# Battery_Shield.net
KiCad netlist of a schematic drawn in EAGLE
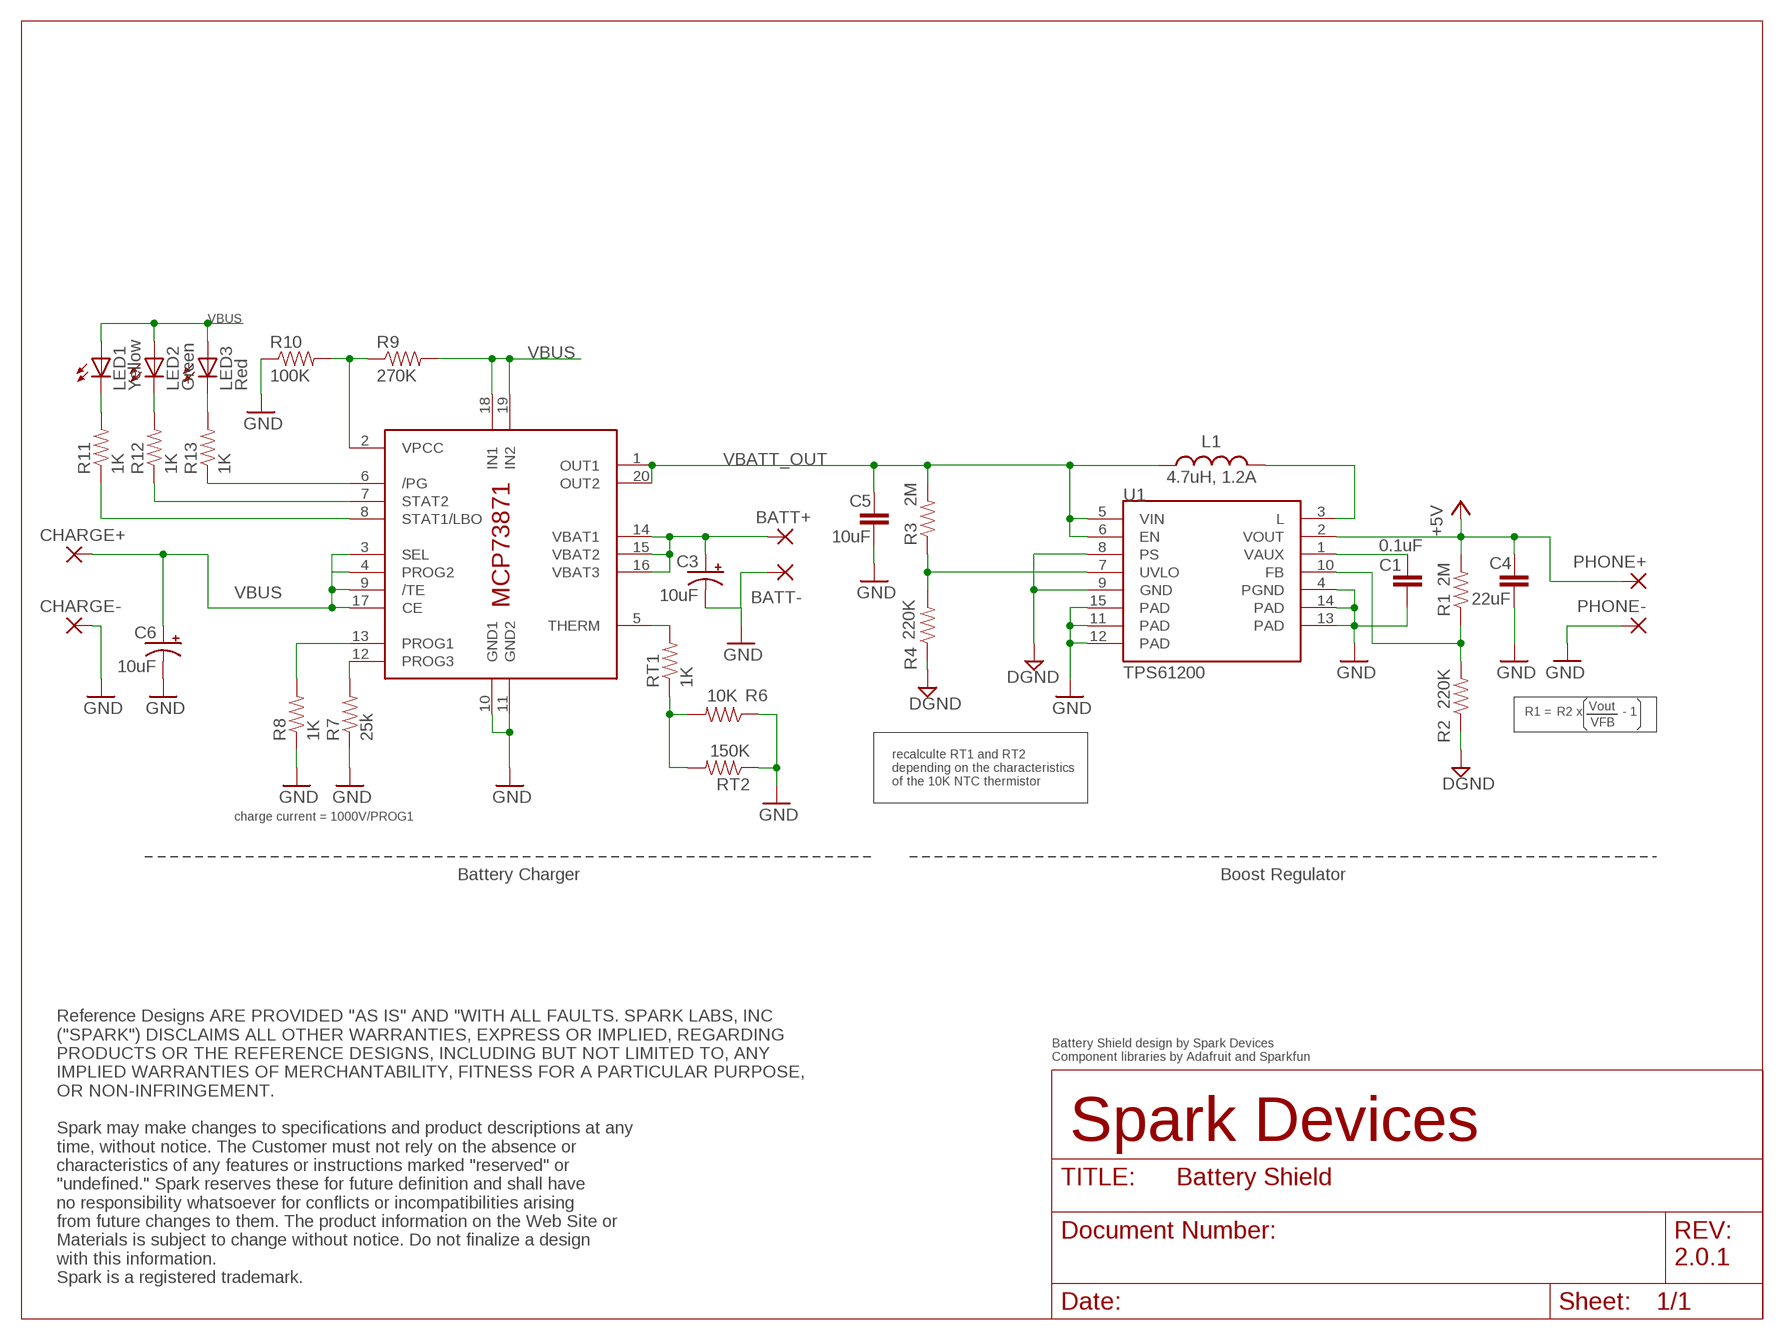
[diagram p0: schematic, sheet 1]

(export (version "E")
  (design (tool "Eeschema 10.0.6"))
  (components
    (comp (ref "BATT+")
      (value "WIREPAD2,15/1,0")
      (footprint "eagle-import:2,15_1,0")
      (libsource (lib "eagle-import") (part "WIREPAD2,15/1,0"))
    )
    (comp (ref "BATT-")
      (value "WIREPAD2,15/1,0")
      (footprint "eagle-import:2,15_1,0")
      (libsource (lib "eagle-import") (part "WIREPAD2,15/1,0"))
    )
    (comp (ref "C1")
      (value "0.1uF")
      (footprint "eagle-import:0402-CAP")
      (libsource (lib "eagle-import") (part "SparkFun-Passives_CAP0402-CAP"))
    )
    (comp (ref "C3")
      (value "10uF")
      (footprint "eagle-import:EIA3216")
      (libsource (lib "eagle-import") (part "10UF-16V-10%(TANT)"))
    )
    (comp (ref "C4")
      (value "22uF")
      (footprint "eagle-import:0805")
      (libsource (lib "eagle-import") (part "SparkFun-Passives_CAP0805"))
    )
    (comp (ref "C5")
      (value "10uF")
      (footprint "eagle-import:1206")
      (libsource (lib "eagle-import") (part "CAP1206"))
    )
    (comp (ref "C6")
      (value "10uF")
      (footprint "eagle-import:EIA3216")
      (fields (field (name "PROD_ID") "CAP-00811"))
      (libsource (lib "eagle-import") (part "10UF-16V-10%(TANT)"))
    )
    (comp (ref "CHARGE+")
      (value "WIREPAD2,15/1,0")
      (footprint "eagle-import:2,15_1,0")
      (libsource (lib "eagle-import") (part "WIREPAD2,15/1,0"))
    )
    (comp (ref "CHARGE-")
      (value "WIREPAD2,15/1,0")
      (footprint "eagle-import:2,15_1,0")
      (libsource (lib "eagle-import") (part "WIREPAD2,15/1,0"))
    )
    (comp (ref "IC1")
      (value "MCP73871")
      (footprint "eagle-import:QFN20")
      (libsource (lib "eagle-import") (part "MCP73871"))
    )
    (comp (ref "L1")
      (value "4.7uH, 1.2A")
      (footprint "eagle-import:CDRH2D09")
      (libsource (lib "eagle-import") (part "INDUCTOR."))
    )
    (comp (ref "LED1")
      (value "Yellow")
      (footprint "eagle-import:LED-0603")
      (libsource (lib "eagle-import") (part "LED0603"))
    )
    (comp (ref "LED2")
      (value "Green")
      (footprint "eagle-import:LED-0603")
      (libsource (lib "eagle-import") (part "LED0603"))
    )
    (comp (ref "LED3")
      (value "Red")
      (footprint "eagle-import:LED-0603")
      (libsource (lib "eagle-import") (part "LED0603"))
    )
    (comp (ref "PHONE+")
      (value "WIREPAD2,15/1,0")
      (footprint "eagle-import:2,15_1,0")
      (libsource (lib "eagle-import") (part "WIREPAD2,15/1,0"))
    )
    (comp (ref "PHONE-")
      (value "WIREPAD2,15/1,0")
      (footprint "eagle-import:2,15_1,0")
      (libsource (lib "eagle-import") (part "WIREPAD2,15/1,0"))
    )
    (comp (ref "R1")
      (value "2M")
      (footprint "eagle-import:0402-RES")
      (libsource (lib "eagle-import") (part "RESISTOR0402-RES"))
    )
    (comp (ref "R2")
      (value "220K")
      (footprint "eagle-import:0402-RES")
      (libsource (lib "eagle-import") (part "RESISTOR0402-RES"))
    )
    (comp (ref "R3")
      (value "2M")
      (footprint "eagle-import:0402-RES")
      (libsource (lib "eagle-import") (part "RESISTOR0402-RES"))
    )
    (comp (ref "R4")
      (value "220K")
      (footprint "eagle-import:0402-RES")
      (libsource (lib "eagle-import") (part "RESISTOR0402-RES"))
    )
    (comp (ref "R6")
      (value "10K")
      (footprint "eagle-import:0402-RES")
      (libsource (lib "eagle-import") (part "RESISTOR0402-RES"))
    )
    (comp (ref "R7")
      (value "25k")
      (footprint "eagle-import:0402-RES")
      (libsource (lib "eagle-import") (part "RESISTOR0402-RES"))
    )
    (comp (ref "R8")
      (value "1K")
      (footprint "eagle-import:0402-RES")
      (libsource (lib "eagle-import") (part "RESISTOR0402-RES"))
    )
    (comp (ref "R9")
      (value "270K")
      (footprint "eagle-import:0402-RES")
      (libsource (lib "eagle-import") (part "RESISTOR0402-RES"))
    )
    (comp (ref "R10")
      (value "100K")
      (footprint "eagle-import:0402-RES")
      (libsource (lib "eagle-import") (part "RESISTOR0402-RES"))
    )
    (comp (ref "R11")
      (value "1K")
      (footprint "eagle-import:0402-RES")
      (libsource (lib "eagle-import") (part "RESISTOR0402-RES"))
    )
    (comp (ref "R12")
      (value "1K")
      (footprint "eagle-import:0402-RES")
      (libsource (lib "eagle-import") (part "RESISTOR0402-RES"))
    )
    (comp (ref "R13")
      (value "1K")
      (footprint "eagle-import:0402-RES")
      (libsource (lib "eagle-import") (part "RESISTOR0402-RES"))
    )
    (comp (ref "RT1")
      (value "1K")
      (footprint "eagle-import:0402-RES")
      (libsource (lib "eagle-import") (part "RESISTOR0402-RES"))
    )
    (comp (ref "RT2")
      (value "150K")
      (footprint "eagle-import:0402-RES")
      (libsource (lib "eagle-import") (part "RESISTOR0402-RES"))
    )
    (comp (ref "U1")
      (value "TPS61200")
      (footprint "eagle-import:QFN-10_PAD")
      (libsource (lib "eagle-import") (part "TPS61200"))
    )
  )
  (nets
    (net (code "1") (name "+5V") (class "Default")
      (node (ref "C4") (pin "1") (pinfunction "1_1") (pintype "passive"))
      (node (ref "PHONE+") (pin "1") (pinfunction "P_1") (pintype "passive"))
      (node (ref "R1") (pin "2") (pinfunction "2_2") (pintype "passive"))
      (node (ref "U1") (pin "2") (pinfunction "VOUT_2") (pintype "passive"))
    )
    (net (code "2") (name "/VBATT_OUT") (class "Default")
      (node (ref "C5") (pin "1") (pinfunction "1_1") (pintype "passive"))
      (node (ref "IC1") (pin "1") (pinfunction "OUT1_1") (pintype "output"))
      (node (ref "IC1") (pin "20") (pinfunction "OUT2_20") (pintype "output"))
      (node (ref "L1") (pin "P$1") (pinfunction "1_P$1") (pintype "passive"))
      (node (ref "R3") (pin "2") (pinfunction "2_2") (pintype "passive"))
      (node (ref "U1") (pin "5") (pinfunction "VIN_5") (pintype "power_in"))
      (node (ref "U1") (pin "6") (pinfunction "EN_6") (pintype "input"))
    )
    (net (code "3") (name "/VBUS") (class "Default")
      (node (ref "C6") (pin "A") (pinfunction "+_A") (pintype "passive"))
      (node (ref "CHARGE+") (pin "1") (pinfunction "P_1") (pintype "passive"))
      (node (ref "IC1") (pin "17") (pinfunction "CE_17") (pintype "input"))
      (node (ref "IC1") (pin "18") (pinfunction "IN1_18") (pintype "input"))
      (node (ref "IC1") (pin "19") (pinfunction "IN2_19") (pintype "input"))
      (node (ref "IC1") (pin "3") (pinfunction "SEL_3") (pintype "input"))
      (node (ref "IC1") (pin "4") (pinfunction "PROG2_4") (pintype "input"))
      (node (ref "IC1") (pin "9") (pinfunction "/TE_9") (pintype "input"))
      (node (ref "LED1") (pin "A") (pinfunction "A_A") (pintype "passive"))
      (node (ref "LED2") (pin "A") (pinfunction "A_A") (pintype "passive"))
      (node (ref "LED3") (pin "A") (pinfunction "A_A") (pintype "passive"))
      (node (ref "R9") (pin "2") (pinfunction "2_2") (pintype "passive"))
    )
    (net (code "4") (name "DGND") (class "Default")
      (node (ref "R2") (pin "1") (pinfunction "1_1") (pintype "passive"))
      (node (ref "R4") (pin "1") (pinfunction "1_1") (pintype "passive"))
      (node (ref "U1") (pin "8") (pinfunction "PS_8") (pintype "input"))
      (node (ref "U1") (pin "9") (pinfunction "GND_9") (pintype "power_in"))
    )
    (net (code "5") (name "GND") (class "Default")
      (node (ref "BATT-") (pin "1") (pinfunction "P_1") (pintype "passive"))
      (node (ref "C1") (pin "2") (pinfunction "2_2") (pintype "passive"))
      (node (ref "C3") (pin "C") (pinfunction "-_C") (pintype "passive"))
      (node (ref "C4") (pin "2") (pinfunction "2_2") (pintype "passive"))
      (node (ref "C5") (pin "2") (pinfunction "2_2") (pintype "passive"))
      (node (ref "C6") (pin "C") (pinfunction "-_C") (pintype "passive"))
      (node (ref "CHARGE-") (pin "1") (pinfunction "P_1") (pintype "passive"))
      (node (ref "IC1") (pin "10") (pinfunction "GND1_10") (pintype "power_in"))
      (node (ref "IC1") (pin "11") (pinfunction "GND2_11") (pintype "power_in"))
      (node (ref "PHONE-") (pin "1") (pinfunction "P_1") (pintype "passive"))
      (node (ref "R10") (pin "1") (pinfunction "1_1") (pintype "passive"))
      (node (ref "R6") (pin "1") (pinfunction "1_1") (pintype "passive"))
      (node (ref "R7") (pin "1") (pinfunction "1_1") (pintype "passive"))
      (node (ref "R8") (pin "1") (pinfunction "1_1") (pintype "passive"))
      (node (ref "RT2") (pin "1") (pinfunction "1_1") (pintype "passive"))
      (node (ref "U1") (pin "11") (pinfunction "PAD_11") (pintype "power_in"))
      (node (ref "U1") (pin "12") (pinfunction "PAD_12") (pintype "power_in"))
      (node (ref "U1") (pin "13") (pinfunction "PAD_13") (pintype "power_in"))
      (node (ref "U1") (pin "14") (pinfunction "PAD_14") (pintype "power_in"))
      (node (ref "U1") (pin "15") (pinfunction "PAD_15") (pintype "power_in"))
      (node (ref "U1") (pin "4") (pinfunction "PGND_4") (pintype "power_in"))
    )
    (net (code "6") (name "Net-(BATT+-P)") (class "Default")
      (node (ref "BATT+") (pin "1") (pinfunction "P_1") (pintype "passive"))
      (node (ref "C3") (pin "A") (pinfunction "+_A") (pintype "passive"))
      (node (ref "IC1") (pin "14") (pinfunction "VBAT1_14") (pintype "output"))
      (node (ref "IC1") (pin "15") (pinfunction "VBAT2_15") (pintype "output"))
      (node (ref "IC1") (pin "16") (pinfunction "VBAT3_16") (pintype "output"))
    )
    (net (code "7") (name "Net-(IC1-PROG1)") (class "Default")
      (node (ref "IC1") (pin "13") (pinfunction "PROG1_13") (pintype "input"))
      (node (ref "R8") (pin "2") (pinfunction "2_2") (pintype "passive"))
    )
    (net (code "8") (name "Net-(IC1-PROG3)") (class "Default")
      (node (ref "IC1") (pin "12") (pinfunction "PROG3_12") (pintype "input"))
      (node (ref "R7") (pin "2") (pinfunction "2_2") (pintype "passive"))
    )
    (net (code "9") (name "Net-(IC1-STAT1{slash}LBO)") (class "Default")
      (node (ref "IC1") (pin "8") (pinfunction "STAT1/LBO_8") (pintype "output"))
      (node (ref "R11") (pin "1") (pinfunction "1_1") (pintype "passive"))
    )
    (net (code "10") (name "Net-(IC1-STAT2)") (class "Default")
      (node (ref "IC1") (pin "7") (pinfunction "STAT2_7") (pintype "output"))
      (node (ref "R12") (pin "1") (pinfunction "1_1") (pintype "passive"))
    )
    (net (code "11") (name "Net-(IC1-THERM)") (class "Default")
      (node (ref "IC1") (pin "5") (pinfunction "THERM_5") (pintype "input"))
      (node (ref "RT1") (pin "2") (pinfunction "2_2") (pintype "passive"))
    )
    (net (code "12") (name "Net-(IC1-VPCC)") (class "Default")
      (node (ref "IC1") (pin "2") (pinfunction "VPCC_2") (pintype "input"))
      (node (ref "R10") (pin "2") (pinfunction "2_2") (pintype "passive"))
      (node (ref "R9") (pin "1") (pinfunction "1_1") (pintype "passive"))
    )
    (net (code "13") (name "Net-(IC1-{slash}PG)") (class "Default")
      (node (ref "IC1") (pin "6") (pinfunction "/PG_6") (pintype "output"))
      (node (ref "R13") (pin "1") (pinfunction "1_1") (pintype "passive"))
    )
    (net (code "14") (name "Net-(L1-2)") (class "Default")
      (node (ref "L1") (pin "P$2") (pinfunction "2_P$2") (pintype "passive"))
      (node (ref "U1") (pin "3") (pinfunction "L_3") (pintype "passive"))
    )
    (net (code "15") (name "Net-(LED1-PadC)") (class "Default")
      (node (ref "LED1") (pin "C") (pinfunction "C_C") (pintype "passive"))
      (node (ref "R11") (pin "2") (pinfunction "2_2") (pintype "passive"))
    )
    (net (code "16") (name "Net-(LED2-PadC)") (class "Default")
      (node (ref "LED2") (pin "C") (pinfunction "C_C") (pintype "passive"))
      (node (ref "R12") (pin "2") (pinfunction "2_2") (pintype "passive"))
    )
    (net (code "17") (name "Net-(LED3-PadC)") (class "Default")
      (node (ref "LED3") (pin "C") (pinfunction "C_C") (pintype "passive"))
      (node (ref "R13") (pin "2") (pinfunction "2_2") (pintype "passive"))
    )
    (net (code "18") (name "Net-(R6-Pad2)") (class "Default")
      (node (ref "R6") (pin "2") (pinfunction "2_2") (pintype "passive"))
      (node (ref "RT1") (pin "1") (pinfunction "1_1") (pintype "passive"))
      (node (ref "RT2") (pin "2") (pinfunction "2_2") (pintype "passive"))
    )
    (net (code "19") (name "Net-(U1-FB)") (class "Default")
      (node (ref "R1") (pin "1") (pinfunction "1_1") (pintype "passive"))
      (node (ref "R2") (pin "2") (pinfunction "2_2") (pintype "passive"))
      (node (ref "U1") (pin "10") (pinfunction "FB_10") (pintype "passive"))
    )
    (net (code "20") (name "Net-(U1-UVLO)") (class "Default")
      (node (ref "R3") (pin "1") (pinfunction "1_1") (pintype "passive"))
      (node (ref "R4") (pin "2") (pinfunction "2_2") (pintype "passive"))
      (node (ref "U1") (pin "7") (pinfunction "UVLO_7") (pintype "passive"))
    )
    (net (code "21") (name "Net-(U1-VAUX)") (class "Default")
      (node (ref "C1") (pin "1") (pinfunction "1_1") (pintype "passive"))
      (node (ref "U1") (pin "1") (pinfunction "VAUX_1") (pintype "passive"))
    )
  )
)
